# SmartSwitch.net
KiCad netlist of a schematic drawn in EAGLE
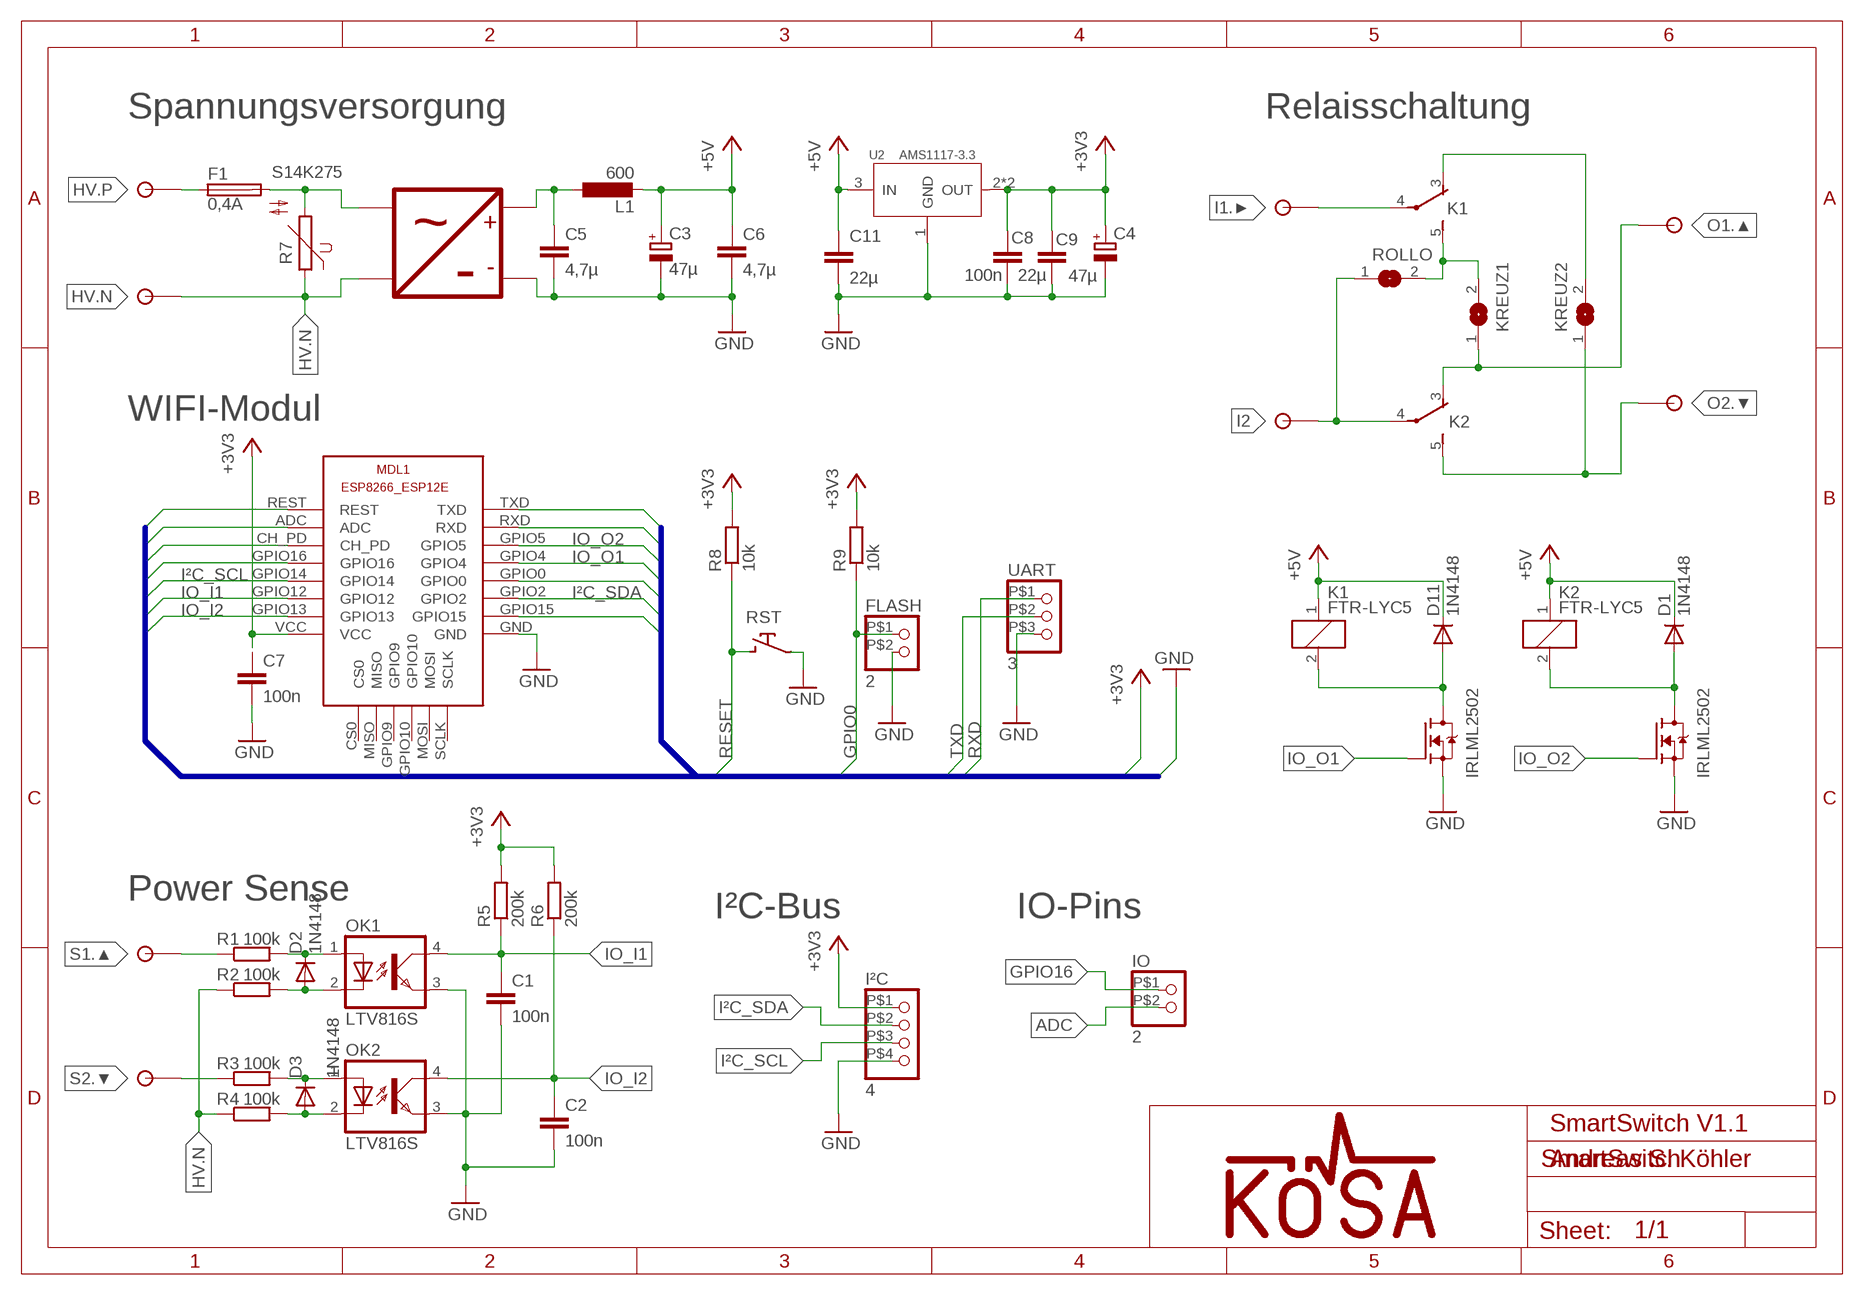
[diagram p0: schematic, sheet 1]

(export (version "E")
  (design (tool "Eeschema 10.0.6"))
  (components
    (comp (ref "C1")
      (value "100n")
      (footprint "eagle-import:C0805")
      (libsource (lib "eagle-import") (part "C-EUC0805"))
    )
    (comp (ref "C2")
      (value "100n")
      (footprint "eagle-import:C0805")
      (libsource (lib "eagle-import") (part "C-EUC0805"))
    )
    (comp (ref "C3")
      (value "47µ")
      (footprint "eagle-import:E2-5")
      (libsource (lib "eagle-import") (part "CPOL-EUE2-5"))
    )
    (comp (ref "C4")
      (value "47µ")
      (footprint "eagle-import:E2-5")
      (libsource (lib "eagle-import") (part "CPOL-EUE2-5"))
    )
    (comp (ref "C5")
      (value "4,7µ")
      (footprint "eagle-import:C0805")
      (libsource (lib "eagle-import") (part "C-EUC0805"))
    )
    (comp (ref "C6")
      (value "4,7µ")
      (footprint "eagle-import:C0805")
      (libsource (lib "eagle-import") (part "C-EUC0805"))
    )
    (comp (ref "C7")
      (value "100n")
      (footprint "eagle-import:C0805")
      (libsource (lib "eagle-import") (part "C-EUC0805"))
    )
    (comp (ref "C8")
      (value "100n")
      (footprint "eagle-import:C0805")
      (libsource (lib "eagle-import") (part "C-EUC0805"))
    )
    (comp (ref "C9")
      (value "22µ")
      (footprint "eagle-import:C0805")
      (libsource (lib "eagle-import") (part "C-EUC0805"))
    )
    (comp (ref "C11")
      (value "22µ")
      (footprint "eagle-import:C0805")
      (libsource (lib "eagle-import") (part "C-EUC0805"))
    )
    (comp (ref "D1")
      (value "1N4148")
      (footprint "eagle-import:SOD323-W")
      (libsource (lib "eagle-import") (part "DIODE-SOD323-W"))
    )
    (comp (ref "D2")
      (value "1N4148")
      (footprint "eagle-import:SOD323-W")
      (libsource (lib "eagle-import") (part "DIODE-SOD323-W"))
    )
    (comp (ref "D3")
      (value "1N4148")
      (footprint "eagle-import:SOD323-W")
      (libsource (lib "eagle-import") (part "DIODE-SOD323-W"))
    )
    (comp (ref "D11")
      (value "1N4148")
      (footprint "eagle-import:SOD323-W")
      (libsource (lib "eagle-import") (part "DIODE-SOD323-W"))
    )
    (comp (ref "F1")
      (value "0,4A")
      (footprint "eagle-import:SMD_FUSE_HOLDER")
      (libsource (lib "eagle-import") (part "SMD_FUSE_HOLDER"))
    )
    (comp (ref "FLASH")
      (value "2")
      (footprint "eagle-import:1X02_SMALL")
      (libsource (lib "eagle-import") (part "PINHD-1X2SMALL"))
    )
    (comp (ref "IO")
      (value "2")
      (footprint "eagle-import:1X02_SMALL")
      (libsource (lib "eagle-import") (part "PINHD-1X2SMALL"))
    )
    (comp (ref "I²C")
      (value "4")
      (footprint "eagle-import:1X04_SMALL")
      (libsource (lib "eagle-import") (part "PINHD-1X4SMALL"))
    )
    (comp (ref "K1")
      (value "FTR-LYC5")
      (footprint "eagle-import:FTR-LYC")
      (libsource (lib "eagle-import") (part "FTR-LYC5"))
    )
    (comp (ref "K2")
      (value "FTR-LYC5")
      (footprint "eagle-import:FTR-LYC")
      (libsource (lib "eagle-import") (part "FTR-LYC5"))
    )
    (comp (ref "KREUZ1")
      (value "SJW")
      (footprint "eagle-import:SJW")
      (libsource (lib "eagle-import") (part "SJW"))
    )
    (comp (ref "KREUZ2")
      (value "SJW")
      (footprint "eagle-import:SJW")
      (libsource (lib "eagle-import") (part "SJW"))
    )
    (comp (ref "L1")
      (value "600")
      (footprint "eagle-import:L3225P")
      (libsource (lib "eagle-import") (part "L-EUL3225P"))
    )
    (comp (ref "MDL1")
      (value "1")
      (footprint "eagle-import:ESP8266-ESP12E")
      (libsource (lib "eagle-import") (part "ESP8266-12EESP8266-ESP12E"))
    )
    (comp (ref "OK1")
      (value "LTV816S")
      (footprint "eagle-import:SMD4")
      (libsource (lib "eagle-import") (part "LTV816S"))
    )
    (comp (ref "OK2")
      (value "LTV816S")
      (footprint "eagle-import:SMD4")
      (libsource (lib "eagle-import") (part "LTV816S"))
    )
    (comp (ref "R1")
      (value "100k")
      (footprint "eagle-import:R1206")
      (libsource (lib "eagle-import") (part "R-EU_R1206"))
    )
    (comp (ref "R2")
      (value "100k")
      (footprint "eagle-import:R1206")
      (libsource (lib "eagle-import") (part "R-EU_R1206"))
    )
    (comp (ref "R3")
      (value "100k")
      (footprint "eagle-import:R1206")
      (libsource (lib "eagle-import") (part "R-EU_R1206"))
    )
    (comp (ref "R4")
      (value "100k")
      (footprint "eagle-import:R1206")
      (libsource (lib "eagle-import") (part "R-EU_R1206"))
    )
    (comp (ref "R5")
      (value "200k")
      (footprint "eagle-import:R1206")
      (libsource (lib "eagle-import") (part "R-EU_R1206"))
    )
    (comp (ref "R6")
      (value "200k")
      (footprint "eagle-import:R1206")
      (libsource (lib "eagle-import") (part "R-EU_R1206"))
    )
    (comp (ref "R7")
      (value "S14K275")
      (footprint "eagle-import:S14K275")
      (libsource (lib "eagle-import") (part "S14K275"))
    )
    (comp (ref "R8")
      (value "10k")
      (footprint "eagle-import:R1206")
      (libsource (lib "eagle-import") (part "R-EU_R1206"))
    )
    (comp (ref "R9")
      (value "10k")
      (footprint "eagle-import:R1206")
      (libsource (lib "eagle-import") (part "R-EU_R1206"))
    )
    (comp (ref "ROLLO")
      (value "SJW")
      (footprint "eagle-import:SJW")
      (libsource (lib "eagle-import") (part "SJW"))
    )
    (comp (ref "RST")
      (value "SMD-TASTER_REICHELT_KMR_231_G_LFS")
      (footprint "eagle-import:SMD-TASTER_REICHELT_KMR_231_G_LFS")
      (libsource (lib "eagle-import") (part "SMD-TASTER_REICHELT_KMR_231_G_LFS"))
    )
    (comp (ref "U$1")
      (value "HLK-PM01")
      (footprint "eagle-import:HLK-PM01")
      (libsource (lib "eagle-import") (part "HLK-PM01"))
    )
    (comp (ref "U$2")
      (value "RND_205-00276")
      (footprint "eagle-import:RND205-00276")
      (libsource (lib "eagle-import") (part "RND_205-00276"))
    )
    (comp (ref "U$3")
      (value "RND_205-00276")
      (footprint "eagle-import:RND205-00276")
      (libsource (lib "eagle-import") (part "RND_205-00276"))
    )
    (comp (ref "U$4")
      (value "RND_205-00276")
      (footprint "eagle-import:RND205-00276")
      (libsource (lib "eagle-import") (part "RND_205-00276"))
    )
    (comp (ref "U$5")
      (value "RND_205-00276")
      (footprint "eagle-import:RND205-00276")
      (libsource (lib "eagle-import") (part "RND_205-00276"))
    )
    (comp (ref "U$7")
      (value "IRLML2502")
      (footprint "eagle-import:SOT23")
      (libsource (lib "eagle-import") (part "IRLML2502"))
    )
    (comp (ref "U$8")
      (value "IRLML2502")
      (footprint "eagle-import:SOT23")
      (libsource (lib "eagle-import") (part "IRLML2502"))
    )
    (comp (ref "U2")
      (value "AMS1117-3.3")
      (footprint "eagle-import:SOT-223")
      (fields (field (name "MPN") "CJT1117-3.3"))
      (libsource (lib "eagle-import") (part "PMIC-CJT1117-3.3(SOT223)"))
    )
    (comp (ref "UART")
      (value "3")
      (footprint "eagle-import:1X03_SMALL")
      (libsource (lib "eagle-import") (part "PINHD-1X3SMALL"))
    )
  )
  (nets
    (net (code "1") (name "+3V3") (class "Default")
      (node (ref "C4") (pin "+") (pinfunction "+_+") (pintype "passive"))
      (node (ref "C7") (pin "1") (pinfunction "1_1") (pintype "passive"))
      (node (ref "C8") (pin "1") (pinfunction "1_1") (pintype "passive"))
      (node (ref "C9") (pin "1") (pinfunction "1_1") (pintype "passive"))
      (node (ref "I²C") (pin "P$1") (pinfunction "1_P$1") (pintype "passive"))
      (node (ref "MDL1") (pin "CH_PD") (pinfunction "CH_PD_CH_PD") (pintype "bidirectional"))
      (node (ref "MDL1") (pin "VCC") (pinfunction "VCC_VCC") (pintype "bidirectional"))
      (node (ref "R5") (pin "2") (pinfunction "2_2") (pintype "passive"))
      (node (ref "R6") (pin "2") (pinfunction "2_2") (pintype "passive"))
      (node (ref "R8") (pin "2") (pinfunction "2_2") (pintype "passive"))
      (node (ref "R9") (pin "2") (pinfunction "2_2") (pintype "passive"))
      (node (ref "U2") (pin "2") (pinfunction "OUT_2") (pintype "bidirectional"))
      (node (ref "U2") (pin "TER") (pinfunction "OUT_TER") (pintype "bidirectional"))
    )
    (net (code "2") (name "+5V") (class "Default")
      (node (ref "C11") (pin "1") (pinfunction "1_1") (pintype "passive"))
      (node (ref "C3") (pin "+") (pinfunction "+_+") (pintype "passive"))
      (node (ref "C6") (pin "1") (pinfunction "1_1") (pintype "passive"))
      (node (ref "D1") (pin "C") (pinfunction "C_C") (pintype "passive"))
      (node (ref "D11") (pin "C") (pinfunction "C_C") (pintype "passive"))
      (node (ref "K1") (pin "1") (pinfunction "1_1") (pintype "passive"))
      (node (ref "K2") (pin "1") (pinfunction "1_1") (pintype "passive"))
      (node (ref "L1") (pin "2") (pinfunction "2_2") (pintype "passive"))
      (node (ref "U2") (pin "3") (pinfunction "IN_3") (pintype "bidirectional"))
    )
    (net (code "3") (name "/GPIO0") (class "Default")
      (node (ref "FLASH") (pin "P$1") (pinfunction "1_P$1") (pintype "passive"))
      (node (ref "MDL1") (pin "GPIO0") (pinfunction "GPIO0_GPIO0") (pintype "bidirectional"))
      (node (ref "R9") (pin "1") (pinfunction "1_1") (pintype "passive"))
    )
    (net (code "4") (name "/RESET") (class "Default")
      (node (ref "MDL1") (pin "REST") (pinfunction "REST_REST") (pintype "bidirectional"))
      (node (ref "R8") (pin "1") (pinfunction "1_1") (pintype "passive"))
      (node (ref "RST") (pin "2_1") (pinfunction "B_2_1") (pintype "bidirectional"))
      (node (ref "RST") (pin "2_2") (pinfunction "B_2_2") (pintype "bidirectional"))
    )
    (net (code "5") (name "/RXD") (class "Default")
      (node (ref "MDL1") (pin "RXD") (pinfunction "RXD_RXD") (pintype "bidirectional"))
      (node (ref "UART") (pin "P$1") (pinfunction "1_P$1") (pintype "passive"))
    )
    (net (code "6") (name "/TXD") (class "Default")
      (node (ref "MDL1") (pin "TXD") (pinfunction "TXD_TXD") (pintype "bidirectional"))
      (node (ref "UART") (pin "P$2") (pinfunction "2_P$2") (pintype "passive"))
    )
    (net (code "7") (name "ADC") (class "Default")
      (node (ref "IO") (pin "P$2") (pinfunction "2_P$2") (pintype "passive"))
      (node (ref "MDL1") (pin "ADC") (pinfunction "ADC_ADC") (pintype "bidirectional"))
    )
    (net (code "8") (name "GND") (class "Default")
      (node (ref "C1") (pin "2") (pinfunction "2_2") (pintype "passive"))
      (node (ref "C11") (pin "2") (pinfunction "2_2") (pintype "passive"))
      (node (ref "C2") (pin "2") (pinfunction "2_2") (pintype "passive"))
      (node (ref "C3") (pin "-") (pinfunction "-_-") (pintype "passive"))
      (node (ref "C4") (pin "-") (pinfunction "-_-") (pintype "passive"))
      (node (ref "C5") (pin "2") (pinfunction "2_2") (pintype "passive"))
      (node (ref "C6") (pin "2") (pinfunction "2_2") (pintype "passive"))
      (node (ref "C7") (pin "2") (pinfunction "2_2") (pintype "passive"))
      (node (ref "C8") (pin "2") (pinfunction "2_2") (pintype "passive"))
      (node (ref "C9") (pin "2") (pinfunction "2_2") (pintype "passive"))
      (node (ref "FLASH") (pin "P$2") (pinfunction "2_P$2") (pintype "passive"))
      (node (ref "I²C") (pin "P$4") (pinfunction "4_P$4") (pintype "passive"))
      (node (ref "MDL1") (pin "GND") (pinfunction "GND_GND") (pintype "bidirectional"))
      (node (ref "MDL1") (pin "GPIO15") (pinfunction "GPIO15_GPIO15") (pintype "bidirectional"))
      (node (ref "OK1") (pin "3") (pinfunction "EMIT_3") (pintype "passive"))
      (node (ref "OK2") (pin "3") (pinfunction "EMIT_3") (pintype "passive"))
      (node (ref "RST") (pin "1_1") (pinfunction "A_1_1") (pintype "bidirectional"))
      (node (ref "RST") (pin "1_2") (pinfunction "A_1_2") (pintype "bidirectional"))
      (node (ref "U$1") (pin "DC-") (pinfunction "DC-_DC-") (pintype "power_in"))
      (node (ref "U$7") (pin "2") (pinfunction "S_2") (pintype "passive"))
      (node (ref "U$8") (pin "2") (pinfunction "S_2") (pintype "passive"))
      (node (ref "U2") (pin "1") (pinfunction "GND_1") (pintype "bidirectional"))
      (node (ref "UART") (pin "P$3") (pinfunction "3_P$3") (pintype "passive"))
    )
    (net (code "9") (name "GPIO16") (class "Default")
      (node (ref "IO") (pin "P$1") (pinfunction "1_P$1") (pintype "passive"))
      (node (ref "MDL1") (pin "GPIO16") (pinfunction "GPIO16_GPIO16") (pintype "bidirectional"))
    )
    (net (code "10") (name "HV.N") (class "Default")
      (node (ref "R2") (pin "1") (pinfunction "1_1") (pintype "passive"))
      (node (ref "R4") (pin "1") (pinfunction "1_1") (pintype "passive"))
      (node (ref "R7") (pin "1") (pinfunction "1_1") (pintype "passive"))
      (node (ref "U$1") (pin "AC2") (pinfunction "AC2_AC2") (pintype "power_in"))
      (node (ref "U$2") (pin "P$2") (pinfunction "P$1_P$2") (pintype "bidirectional"))
    )
    (net (code "11") (name "HV.P") (class "Default")
      (node (ref "F1") (pin "P$1") (pinfunction "1_P$1") (pintype "passive"))
      (node (ref "U$2") (pin "P$1") (pinfunction "P$1_P$1") (pintype "bidirectional"))
    )
    (net (code "12") (name "I1.►") (class "Default")
      (node (ref "K1") (pin "4") (pinfunction "P_4") (pintype "passive"))
      (node (ref "U$4") (pin "P$1") (pinfunction "P$1_P$1") (pintype "bidirectional"))
    )
    (net (code "13") (name "I2") (class "Default")
      (node (ref "K2") (pin "4") (pinfunction "P_4") (pintype "passive"))
      (node (ref "ROLLO") (pin "1") (pinfunction "1_1") (pintype "passive"))
      (node (ref "U$3") (pin "P$1") (pinfunction "P$1_P$1") (pintype "bidirectional"))
    )
    (net (code "14") (name "IO_I1") (class "Default")
      (node (ref "C1") (pin "1") (pinfunction "1_1") (pintype "passive"))
      (node (ref "MDL1") (pin "GPIO12") (pinfunction "GPIO12_GPIO12") (pintype "bidirectional"))
      (node (ref "OK1") (pin "4") (pinfunction "COL_4") (pintype "passive"))
      (node (ref "R5") (pin "1") (pinfunction "1_1") (pintype "passive"))
    )
    (net (code "15") (name "IO_I2") (class "Default")
      (node (ref "C2") (pin "1") (pinfunction "1_1") (pintype "passive"))
      (node (ref "MDL1") (pin "GPIO13") (pinfunction "GPIO13_GPIO13") (pintype "bidirectional"))
      (node (ref "OK2") (pin "4") (pinfunction "COL_4") (pintype "passive"))
      (node (ref "R6") (pin "1") (pinfunction "1_1") (pintype "passive"))
    )
    (net (code "16") (name "IO_O1") (class "Default")
      (node (ref "MDL1") (pin "GPIO4") (pinfunction "GPIO4_GPIO4") (pintype "bidirectional"))
      (node (ref "U$7") (pin "1") (pinfunction "G_1") (pintype "passive"))
    )
    (net (code "17") (name "IO_O2") (class "Default")
      (node (ref "MDL1") (pin "GPIO5") (pinfunction "GPIO5_GPIO5") (pintype "bidirectional"))
      (node (ref "U$8") (pin "1") (pinfunction "G_1") (pintype "passive"))
    )
    (net (code "18") (name "I²C_SCL") (class "Default")
      (node (ref "I²C") (pin "P$3") (pinfunction "3_P$3") (pintype "passive"))
      (node (ref "MDL1") (pin "GPIO14") (pinfunction "GPIO14_GPIO14") (pintype "bidirectional"))
    )
    (net (code "19") (name "I²C_SDA") (class "Default")
      (node (ref "I²C") (pin "P$2") (pinfunction "2_P$2") (pintype "passive"))
      (node (ref "MDL1") (pin "GPIO2") (pinfunction "GPIO2_GPIO2") (pintype "bidirectional"))
    )
    (net (code "20") (name "Net-(C5-Pad1)") (class "Default")
      (node (ref "C5") (pin "1") (pinfunction "1_1") (pintype "passive"))
      (node (ref "L1") (pin "1") (pinfunction "1_1") (pintype "passive"))
      (node (ref "U$1") (pin "DC+") (pinfunction "DC+_DC+") (pintype "power_in"))
    )
    (net (code "21") (name "Net-(F1-2)") (class "Default")
      (node (ref "F1") (pin "P$2") (pinfunction "2_P$2") (pintype "passive"))
      (node (ref "R7") (pin "2") (pinfunction "2_2") (pintype "passive"))
      (node (ref "U$1") (pin "AC1") (pinfunction "AC1_AC1") (pintype "power_in"))
    )
    (net (code "22") (name "Net-(K1A-O)") (class "Default")
      (node (ref "K1") (pin "3") (pinfunction "O_3") (pintype "passive"))
      (node (ref "KREUZ2") (pin "2") (pinfunction "2_2") (pintype "passive"))
    )
    (net (code "23") (name "Net-(K1A-S)") (class "Default")
      (node (ref "K1") (pin "5") (pinfunction "S_5") (pintype "passive"))
      (node (ref "KREUZ1") (pin "2") (pinfunction "2_2") (pintype "passive"))
      (node (ref "ROLLO") (pin "2") (pinfunction "2_2") (pintype "passive"))
    )
    (net (code "24") (name "Net-(OK1-A)") (class "Default")
      (node (ref "D2") (pin "C") (pinfunction "C_C") (pintype "passive"))
      (node (ref "OK1") (pin "1") (pinfunction "A_1") (pintype "passive"))
      (node (ref "R1") (pin "2") (pinfunction "2_2") (pintype "passive"))
    )
    (net (code "25") (name "Net-(OK1-C)") (class "Default")
      (node (ref "D2") (pin "A") (pinfunction "A_A") (pintype "passive"))
      (node (ref "OK1") (pin "2") (pinfunction "C_2") (pintype "passive"))
      (node (ref "R2") (pin "2") (pinfunction "2_2") (pintype "passive"))
    )
    (net (code "26") (name "Net-(OK2-A)") (class "Default")
      (node (ref "D3") (pin "C") (pinfunction "C_C") (pintype "passive"))
      (node (ref "OK2") (pin "1") (pinfunction "A_1") (pintype "passive"))
      (node (ref "R3") (pin "2") (pinfunction "2_2") (pintype "passive"))
    )
    (net (code "27") (name "Net-(OK2-C)") (class "Default")
      (node (ref "D3") (pin "A") (pinfunction "A_A") (pintype "passive"))
      (node (ref "OK2") (pin "2") (pinfunction "C_2") (pintype "passive"))
      (node (ref "R4") (pin "2") (pinfunction "2_2") (pintype "passive"))
    )
    (net (code "28") (name "Net-(U$7-D)") (class "Default")
      (node (ref "D11") (pin "A") (pinfunction "A_A") (pintype "passive"))
      (node (ref "K1") (pin "2") (pinfunction "2_2") (pintype "passive"))
      (node (ref "U$7") (pin "3") (pinfunction "D_3") (pintype "passive"))
    )
    (net (code "29") (name "Net-(U$8-D)") (class "Default")
      (node (ref "D1") (pin "A") (pinfunction "A_A") (pintype "passive"))
      (node (ref "K2") (pin "2") (pinfunction "2_2") (pintype "passive"))
      (node (ref "U$8") (pin "3") (pinfunction "D_3") (pintype "passive"))
    )
    (net (code "30") (name "O1.▲") (class "Default")
      (node (ref "K2") (pin "3") (pinfunction "O_3") (pintype "passive"))
      (node (ref "KREUZ1") (pin "1") (pinfunction "1_1") (pintype "passive"))
      (node (ref "U$3") (pin "P$2") (pinfunction "P$1_P$2") (pintype "bidirectional"))
    )
    (net (code "31") (name "O2.▼") (class "Default")
      (node (ref "K2") (pin "5") (pinfunction "S_5") (pintype "passive"))
      (node (ref "KREUZ2") (pin "1") (pinfunction "1_1") (pintype "passive"))
      (node (ref "U$4") (pin "P$2") (pinfunction "P$1_P$2") (pintype "bidirectional"))
    )
    (net (code "32") (name "S1.▲") (class "Default")
      (node (ref "R1") (pin "1") (pinfunction "1_1") (pintype "passive"))
      (node (ref "U$5") (pin "P$2") (pinfunction "P$1_P$2") (pintype "bidirectional"))
    )
    (net (code "33") (name "S2.▼") (class "Default")
      (node (ref "R3") (pin "1") (pinfunction "1_1") (pintype "passive"))
      (node (ref "U$5") (pin "P$1") (pinfunction "P$1_P$1") (pintype "bidirectional"))
    )
    (net (code "34") (name "unconnected-(MDL1-PadCS0)") (class "Default")
      (node (ref "MDL1") (pin "CS0") (pinfunction "CS0_CS0") (pintype "bidirectional"))
    )
    (net (code "35") (name "unconnected-(MDL1-PadGPIO9)") (class "Default")
      (node (ref "MDL1") (pin "GPIO9") (pinfunction "GPIO9_GPIO9") (pintype "bidirectional"))
    )
    (net (code "36") (name "unconnected-(MDL1-PadGPIO10)") (class "Default")
      (node (ref "MDL1") (pin "GPIO10") (pinfunction "GPIO10_GPIO10") (pintype "bidirectional"))
    )
    (net (code "37") (name "unconnected-(MDL1-PadMISO)") (class "Default")
      (node (ref "MDL1") (pin "MISO") (pinfunction "MISO_MISO") (pintype "bidirectional"))
    )
    (net (code "38") (name "unconnected-(MDL1-PadMOSI)") (class "Default")
      (node (ref "MDL1") (pin "MOSI") (pinfunction "MOSI_MOSI") (pintype "bidirectional"))
    )
    (net (code "39") (name "unconnected-(MDL1-PadSCLK)") (class "Default")
      (node (ref "MDL1") (pin "SCLK") (pinfunction "SCLK_SCLK") (pintype "bidirectional"))
    )
  )
)
